# neuzplaits.net
KiCad netlist of a schematic drawn in EAGLE
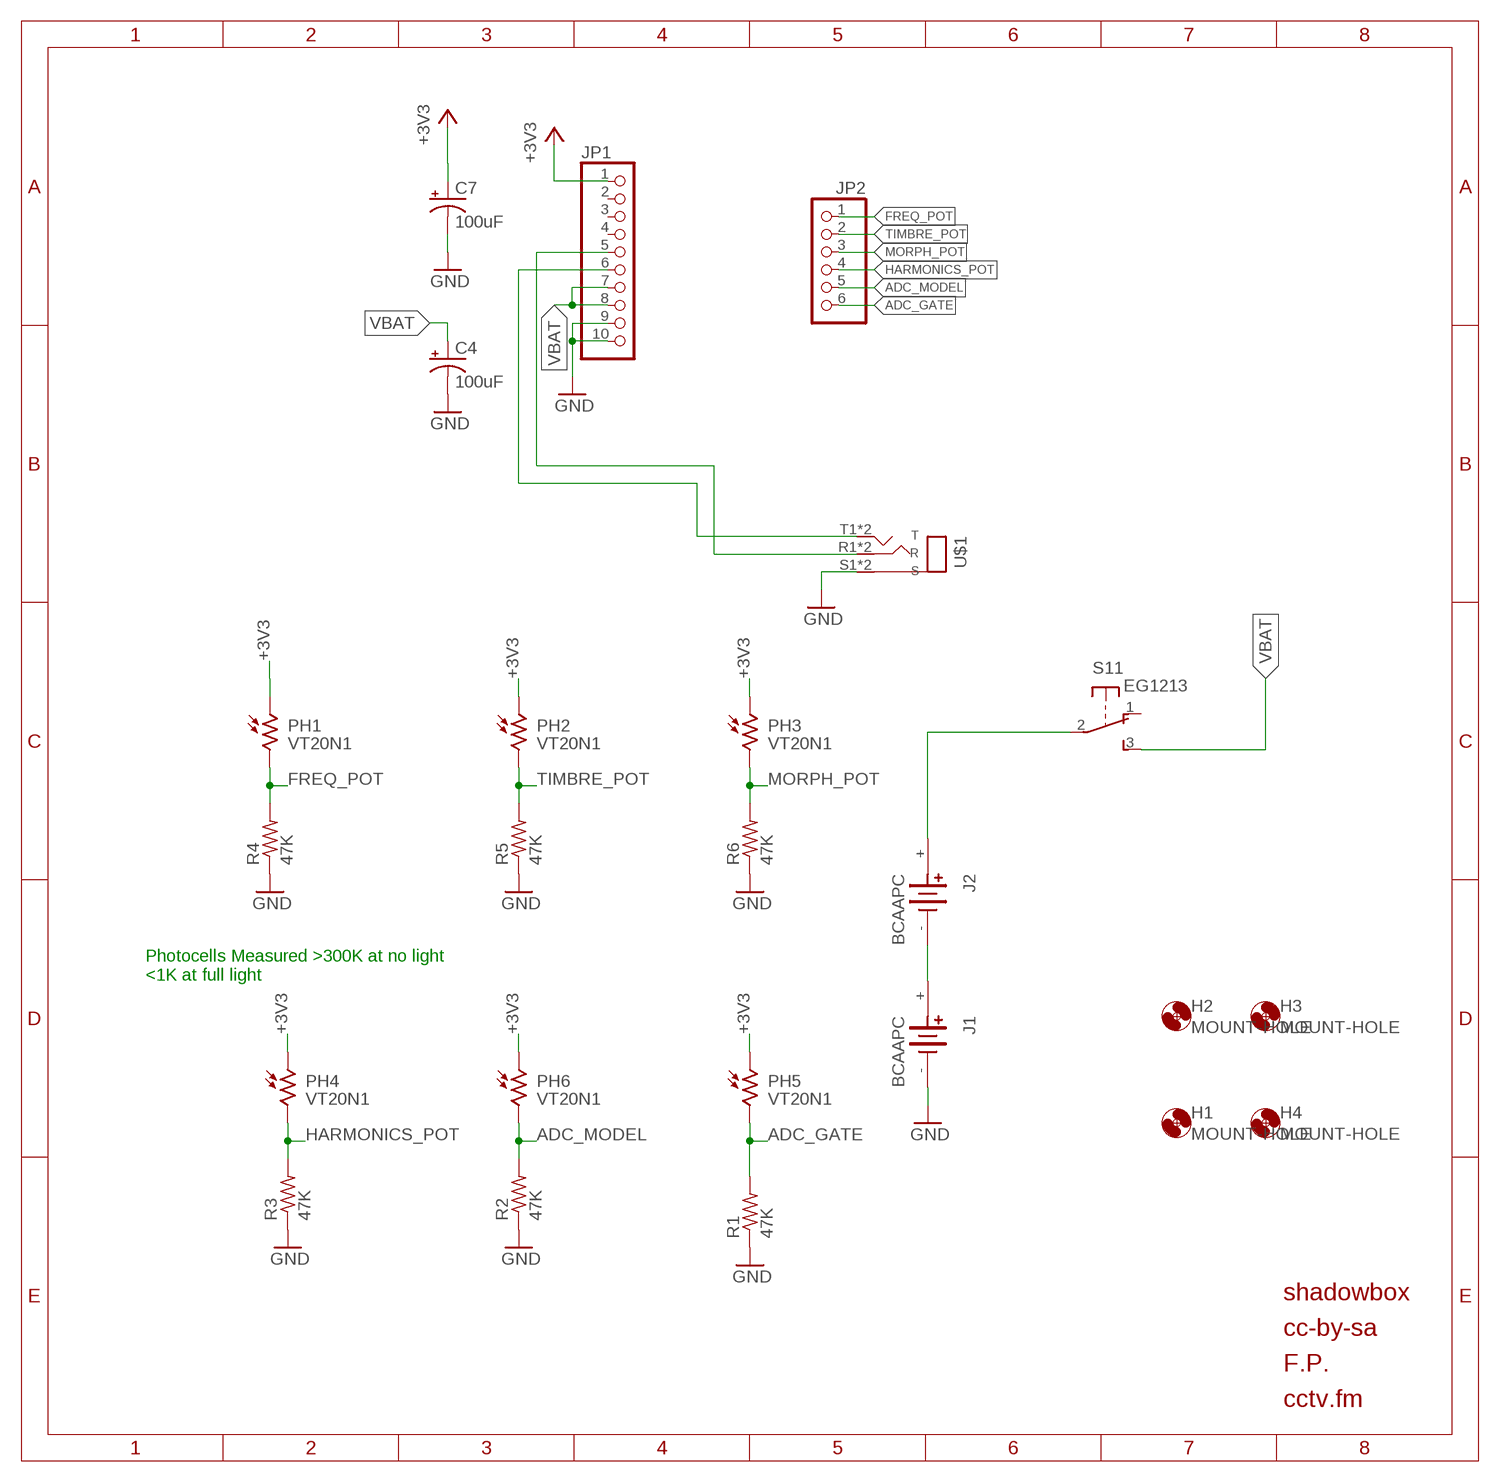
[diagram p0: schematic, sheet 1]

(export (version "E")
  (design (tool "Eeschema 10.0.6"))
  (components
    (comp (ref "C4")
      (value "100uF")
      (footprint "eagle-import:E2,5-6")
      (libsource (lib "eagle-import") (part "CPOL-USE2.5-6"))
    )
    (comp (ref "C7")
      (value "100uF")
      (footprint "eagle-import:E2,5-6")
      (libsource (lib "eagle-import") (part "CPOL-USE2.5-6"))
    )
    (comp (ref "H1")
      (value "MOUNT-HOLE")
      (footprint "eagle-import:3,0TINY")
      (libsource (lib "eagle-import") (part "MOUNT-HOLE3.0TINY"))
    )
    (comp (ref "H2")
      (value "MOUNT-HOLE")
      (footprint "eagle-import:3,0TINY")
      (libsource (lib "eagle-import") (part "MOUNT-HOLE3.0TINY"))
    )
    (comp (ref "H3")
      (value "MOUNT-HOLE")
      (footprint "eagle-import:3,0TINY")
      (libsource (lib "eagle-import") (part "MOUNT-HOLE3.0TINY"))
    )
    (comp (ref "H4")
      (value "MOUNT-HOLE")
      (footprint "eagle-import:3,0TINY")
      (libsource (lib "eagle-import") (part "MOUNT-HOLE3.0TINY"))
    )
    (comp (ref "J1")
      (value "BCAAPC")
      (footprint "eagle-import:MPD_BCAAPC")
      (fields (field (name "MF") "MPD"))
      (libsource (lib "eagle-import") (part "BCAAPC"))
    )
    (comp (ref "J2")
      (value "BCAAPC")
      (footprint "eagle-import:MPD_BCAAPC")
      (fields (field (name "MF") "MPD"))
      (libsource (lib "eagle-import") (part "BCAAPC"))
    )
    (comp (ref "JP1")
      (value "PINHD-1X10")
      (footprint "eagle-import:1X10")
      (libsource (lib "eagle-import") (part "PINHD-1X10"))
    )
    (comp (ref "JP2")
      (value "PINHD-1X6")
      (footprint "eagle-import:1X06")
      (libsource (lib "eagle-import") (part "PINHD-1X6"))
    )
    (comp (ref "PH1")
      (value "VT20N1")
      (footprint "eagle-import:TO46-VT200")
      (libsource (lib "eagle-import") (part "VT20N1"))
    )
    (comp (ref "PH2")
      (value "VT20N1")
      (footprint "eagle-import:TO46-VT200")
      (libsource (lib "eagle-import") (part "VT20N1"))
    )
    (comp (ref "PH3")
      (value "VT20N1")
      (footprint "eagle-import:TO46-VT200")
      (libsource (lib "eagle-import") (part "VT20N1"))
    )
    (comp (ref "PH4")
      (value "VT20N1")
      (footprint "eagle-import:TO46-VT200")
      (libsource (lib "eagle-import") (part "VT20N1"))
    )
    (comp (ref "PH5")
      (value "VT20N1")
      (footprint "eagle-import:TO46-VT200")
      (libsource (lib "eagle-import") (part "VT20N1"))
    )
    (comp (ref "PH6")
      (value "VT20N1")
      (footprint "eagle-import:TO46-VT200")
      (libsource (lib "eagle-import") (part "VT20N1"))
    )
    (comp (ref "R1")
      (value "47K")
      (footprint "eagle-import:0204_7")
      (libsource (lib "eagle-import") (part "RES-7.5-EASYSOLDER"))
    )
    (comp (ref "R2")
      (value "47K")
      (footprint "eagle-import:0204_7")
      (libsource (lib "eagle-import") (part "RES-7.5-EASYSOLDER"))
    )
    (comp (ref "R3")
      (value "47K")
      (footprint "eagle-import:0204_7")
      (libsource (lib "eagle-import") (part "RES-7.5-EASYSOLDER"))
    )
    (comp (ref "R4")
      (value "47K")
      (footprint "eagle-import:0204_7")
      (libsource (lib "eagle-import") (part "RES-7.5-EASYSOLDER"))
    )
    (comp (ref "R5")
      (value "47K")
      (footprint "eagle-import:0204_7")
      (libsource (lib "eagle-import") (part "RES-7.5-EASYSOLDER"))
    )
    (comp (ref "R6")
      (value "47K")
      (footprint "eagle-import:0204_7")
      (libsource (lib "eagle-import") (part "RES-7.5-EASYSOLDER"))
    )
    (comp (ref "S1")
      (value "EG1213")
      (footprint "eagle-import:EG1213")
      (libsource (lib "eagle-import") (part "EG1213"))
    )
    (comp (ref "U$1")
      (value "PJ-3136-B")
      (footprint "eagle-import:PJ-3136-B")
      (libsource (lib "eagle-import") (part "PJ-3136-B"))
    )
  )
  (nets
    (net (code "1") (name "+3V3") (class "Default")
      (node (ref "C7") (pin "+") (pinfunction "+_+") (pintype "passive"))
      (node (ref "JP1") (pin "1") (pinfunction "1_1") (pintype "passive"))
      (node (ref "PH1") (pin "1") (pinfunction "1_1") (pintype "passive"))
      (node (ref "PH2") (pin "1") (pinfunction "1_1") (pintype "passive"))
      (node (ref "PH3") (pin "1") (pinfunction "1_1") (pintype "passive"))
      (node (ref "PH4") (pin "1") (pinfunction "1_1") (pintype "passive"))
      (node (ref "PH5") (pin "1") (pinfunction "1_1") (pintype "passive"))
      (node (ref "PH6") (pin "1") (pinfunction "1_1") (pintype "passive"))
    )
    (net (code "2") (name "ADC_GATE") (class "Default")
      (node (ref "JP2") (pin "6") (pinfunction "6_6") (pintype "passive"))
      (node (ref "PH5") (pin "2") (pinfunction "2_2") (pintype "passive"))
      (node (ref "R1") (pin "2") (pinfunction "2_2") (pintype "passive"))
    )
    (net (code "3") (name "ADC_MODEL") (class "Default")
      (node (ref "JP2") (pin "5") (pinfunction "5_5") (pintype "passive"))
      (node (ref "PH6") (pin "2") (pinfunction "2_2") (pintype "passive"))
      (node (ref "R2") (pin "2") (pinfunction "2_2") (pintype "passive"))
    )
    (net (code "4") (name "FREQ_POT") (class "Default")
      (node (ref "JP2") (pin "1") (pinfunction "1_1") (pintype "passive"))
      (node (ref "PH1") (pin "2") (pinfunction "2_2") (pintype "passive"))
      (node (ref "R4") (pin "2") (pinfunction "2_2") (pintype "passive"))
    )
    (net (code "5") (name "GND") (class "Default")
      (node (ref "C4") (pin "-") (pinfunction "-_-") (pintype "passive"))
      (node (ref "C7") (pin "-") (pinfunction "-_-") (pintype "passive"))
      (node (ref "J1") (pin "-") (pinfunction "-_-") (pintype "passive"))
      (node (ref "JP1") (pin "10") (pinfunction "10_10") (pintype "passive"))
      (node (ref "JP1") (pin "9") (pinfunction "9_9") (pintype "passive"))
      (node (ref "R1") (pin "1") (pinfunction "1_1") (pintype "passive"))
      (node (ref "R2") (pin "1") (pinfunction "1_1") (pintype "passive"))
      (node (ref "R3") (pin "1") (pinfunction "1_1") (pintype "passive"))
      (node (ref "R4") (pin "1") (pinfunction "1_1") (pintype "passive"))
      (node (ref "R5") (pin "1") (pinfunction "1_1") (pintype "passive"))
      (node (ref "R6") (pin "1") (pinfunction "1_1") (pintype "passive"))
      (node (ref "U$1") (pin "S1") (pinfunction "S_S1") (pintype "passive"))
      (node (ref "U$1") (pin "S2") (pinfunction "S_S2") (pintype "passive"))
    )
    (net (code "6") (name "HARMONICS_POT") (class "Default")
      (node (ref "JP2") (pin "4") (pinfunction "4_4") (pintype "passive"))
      (node (ref "PH4") (pin "2") (pinfunction "2_2") (pintype "passive"))
      (node (ref "R3") (pin "2") (pinfunction "2_2") (pintype "passive"))
    )
    (net (code "7") (name "MORPH_POT") (class "Default")
      (node (ref "JP2") (pin "3") (pinfunction "3_3") (pintype "passive"))
      (node (ref "PH3") (pin "2") (pinfunction "2_2") (pintype "passive"))
      (node (ref "R6") (pin "2") (pinfunction "2_2") (pintype "passive"))
    )
    (net (code "8") (name "Net-(J1-Pad+)") (class "Default")
      (node (ref "J1") (pin "+") (pinfunction "+_+") (pintype "passive"))
      (node (ref "J2") (pin "-") (pinfunction "-_-") (pintype "passive"))
    )
    (net (code "9") (name "Net-(JP1-Pad5)") (class "Default")
      (node (ref "JP1") (pin "5") (pinfunction "5_5") (pintype "passive"))
      (node (ref "U$1") (pin "R1") (pinfunction "R_R1") (pintype "passive"))
      (node (ref "U$1") (pin "R2") (pinfunction "R_R2") (pintype "passive"))
    )
    (net (code "10") (name "Net-(JP1-Pad6)") (class "Default")
      (node (ref "JP1") (pin "6") (pinfunction "6_6") (pintype "passive"))
      (node (ref "U$1") (pin "T1") (pinfunction "T_T1") (pintype "passive"))
      (node (ref "U$1") (pin "T2") (pinfunction "T_T2") (pintype "passive"))
    )
    (net (code "11") (name "Net-(S1A-P)") (class "Default")
      (node (ref "J2") (pin "+") (pinfunction "+_+") (pintype "passive"))
      (node (ref "S1") (pin "2") (pinfunction "P_2") (pintype "passive"))
    )
    (net (code "12") (name "TIMBRE_POT") (class "Default")
      (node (ref "JP2") (pin "2") (pinfunction "2_2") (pintype "passive"))
      (node (ref "PH2") (pin "2") (pinfunction "2_2") (pintype "passive"))
      (node (ref "R5") (pin "2") (pinfunction "2_2") (pintype "passive"))
    )
    (net (code "13") (name "VBAT") (class "Default")
      (node (ref "C4") (pin "+") (pinfunction "+_+") (pintype "passive"))
      (node (ref "JP1") (pin "7") (pinfunction "7_7") (pintype "passive"))
      (node (ref "JP1") (pin "8") (pinfunction "8_8") (pintype "passive"))
      (node (ref "S1") (pin "3") (pinfunction "S_3") (pintype "passive"))
    )
    (net (code "14") (name "unconnected-(JP1-Pad2)") (class "Default")
      (node (ref "JP1") (pin "2") (pinfunction "2_2") (pintype "passive"))
    )
    (net (code "15") (name "unconnected-(JP1-Pad3)") (class "Default")
      (node (ref "JP1") (pin "3") (pinfunction "3_3") (pintype "passive"))
    )
    (net (code "16") (name "unconnected-(JP1-Pad4)") (class "Default")
      (node (ref "JP1") (pin "4") (pinfunction "4_4") (pintype "passive"))
    )
    (net (code "17") (name "unconnected-(S1A-O-Pad1)") (class "Default")
      (node (ref "S1") (pin "1") (pinfunction "O_1") (pintype "passive"))
    )
  )
)
